# 07_Secure_Element.net
KiCad netlist of a schematic drawn in Altium Designer
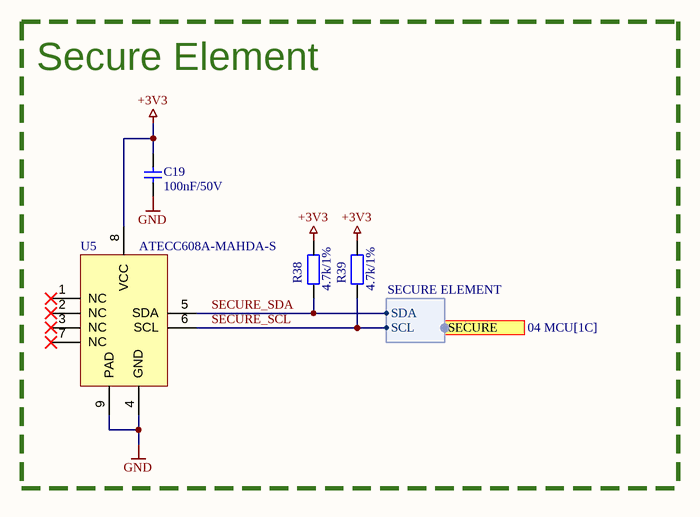
[diagram p0: 07 Secure Element.SchDoc]

(export (version "E")
  (design (tool "Eeschema 10.0.6"))
  (components
    (comp (ref "C19")
      (value "100nF/50V")
      (footprint "CAPC1005X06M-0402")
      (description "0.1 µF ±10% 50V Ceramic Capacitor X7R 0402 (1005 Metric)")
      (fields (field (name "MPN") "GRM155R71H104KE14D"))
      (libsource (lib "Symbol") (part "GRM155R71H104KE14D"))
    )
    (comp (ref "R38")
      (value "4.7k/1%")
      (footprint "RESC1005X04M-0402")
      (description "4.7 kOhms ±1% 0.063W, 1/16W Chip Resistor 0402 (1005 Metric) Moisture Resistant Thick Film")
      (fields (field (name "MPN") "RC0402FR-074K7L"))
      (libsource (lib "Symbol") (part "RC0402FR-074K7L"))
    )
    (comp (ref "R39")
      (value "4.7k/1%")
      (footprint "RESC1005X04M-0402")
      (description "4.7 kOhms ±1% 0.063W, 1/16W Chip Resistor 0402 (1005 Metric) Moisture Resistant Thick Film")
      (fields (field (name "MPN") "RC0402FR-074K7L"))
      (libsource (lib "Symbol") (part "RC0402FR-074K7L"))
    )
    (comp (ref "U5")
      (value "ATECC608A-MAHDA-S")
      (footprint "SON50P200X60_HS-9N")
      (description "Authentication Chip 8-UDFN (2x3)")
      (libsource (lib "Symbol") (part "ATECC608A-MAHDA-S"))
    )
  )
  (nets
    (net (code "3") (name "+3V3") (class "Default")
      (node (ref "C19") (pin "2") (pinfunction "2_2") (pintype "passive"))
      (node (ref "R38") (pin "2") (pinfunction "2_2") (pintype "passive"))
      (node (ref "R39") (pin "2") (pinfunction "2_2") (pintype "passive"))
      (node (ref "U5") (pin "8") (pinfunction "VCC_8") (pintype "passive"))
    )
    (net (code "4") (name "/SECURE_SCL") (class "Default")
      (node (ref "R39") (pin "1") (pinfunction "1_1") (pintype "passive"))
      (node (ref "U5") (pin "6") (pinfunction "SCL_6") (pintype "passive"))
    )
    (net (code "5") (name "/SECURE_SDA") (class "Default")
      (node (ref "R38") (pin "1") (pinfunction "1_1") (pintype "passive"))
      (node (ref "U5") (pin "5") (pinfunction "SDA_5") (pintype "passive"))
    )
    (net (code "7") (name "GND") (class "Default")
      (node (ref "C19") (pin "1") (pinfunction "1_1") (pintype "passive"))
      (node (ref "U5") (pin "4") (pinfunction "GND_4") (pintype "passive"))
      (node (ref "U5") (pin "9") (pinfunction "PAD_9") (pintype "passive"))
    )
    (net (code "8") (name "unconnected-(U5-NC-Pad1)") (class "Default")
      (node (ref "U5") (pin "1") (pinfunction "NC_1") (pintype "passive+no_connect"))
    )
    (net (code "9") (name "unconnected-(U5-NC-Pad2)") (class "Default")
      (node (ref "U5") (pin "2") (pinfunction "NC_2") (pintype "passive+no_connect"))
    )
    (net (code "10") (name "unconnected-(U5-NC-Pad3)") (class "Default")
      (node (ref "U5") (pin "3") (pinfunction "NC_3") (pintype "passive+no_connect"))
    )
    (net (code "11") (name "unconnected-(U5-NC-Pad7)") (class "Default")
      (node (ref "U5") (pin "7") (pinfunction "NC_7") (pintype "passive+no_connect"))
    )
  )
)
